# mdriver_v2.net
KiCad netlist of a schematic drawn in EAGLE
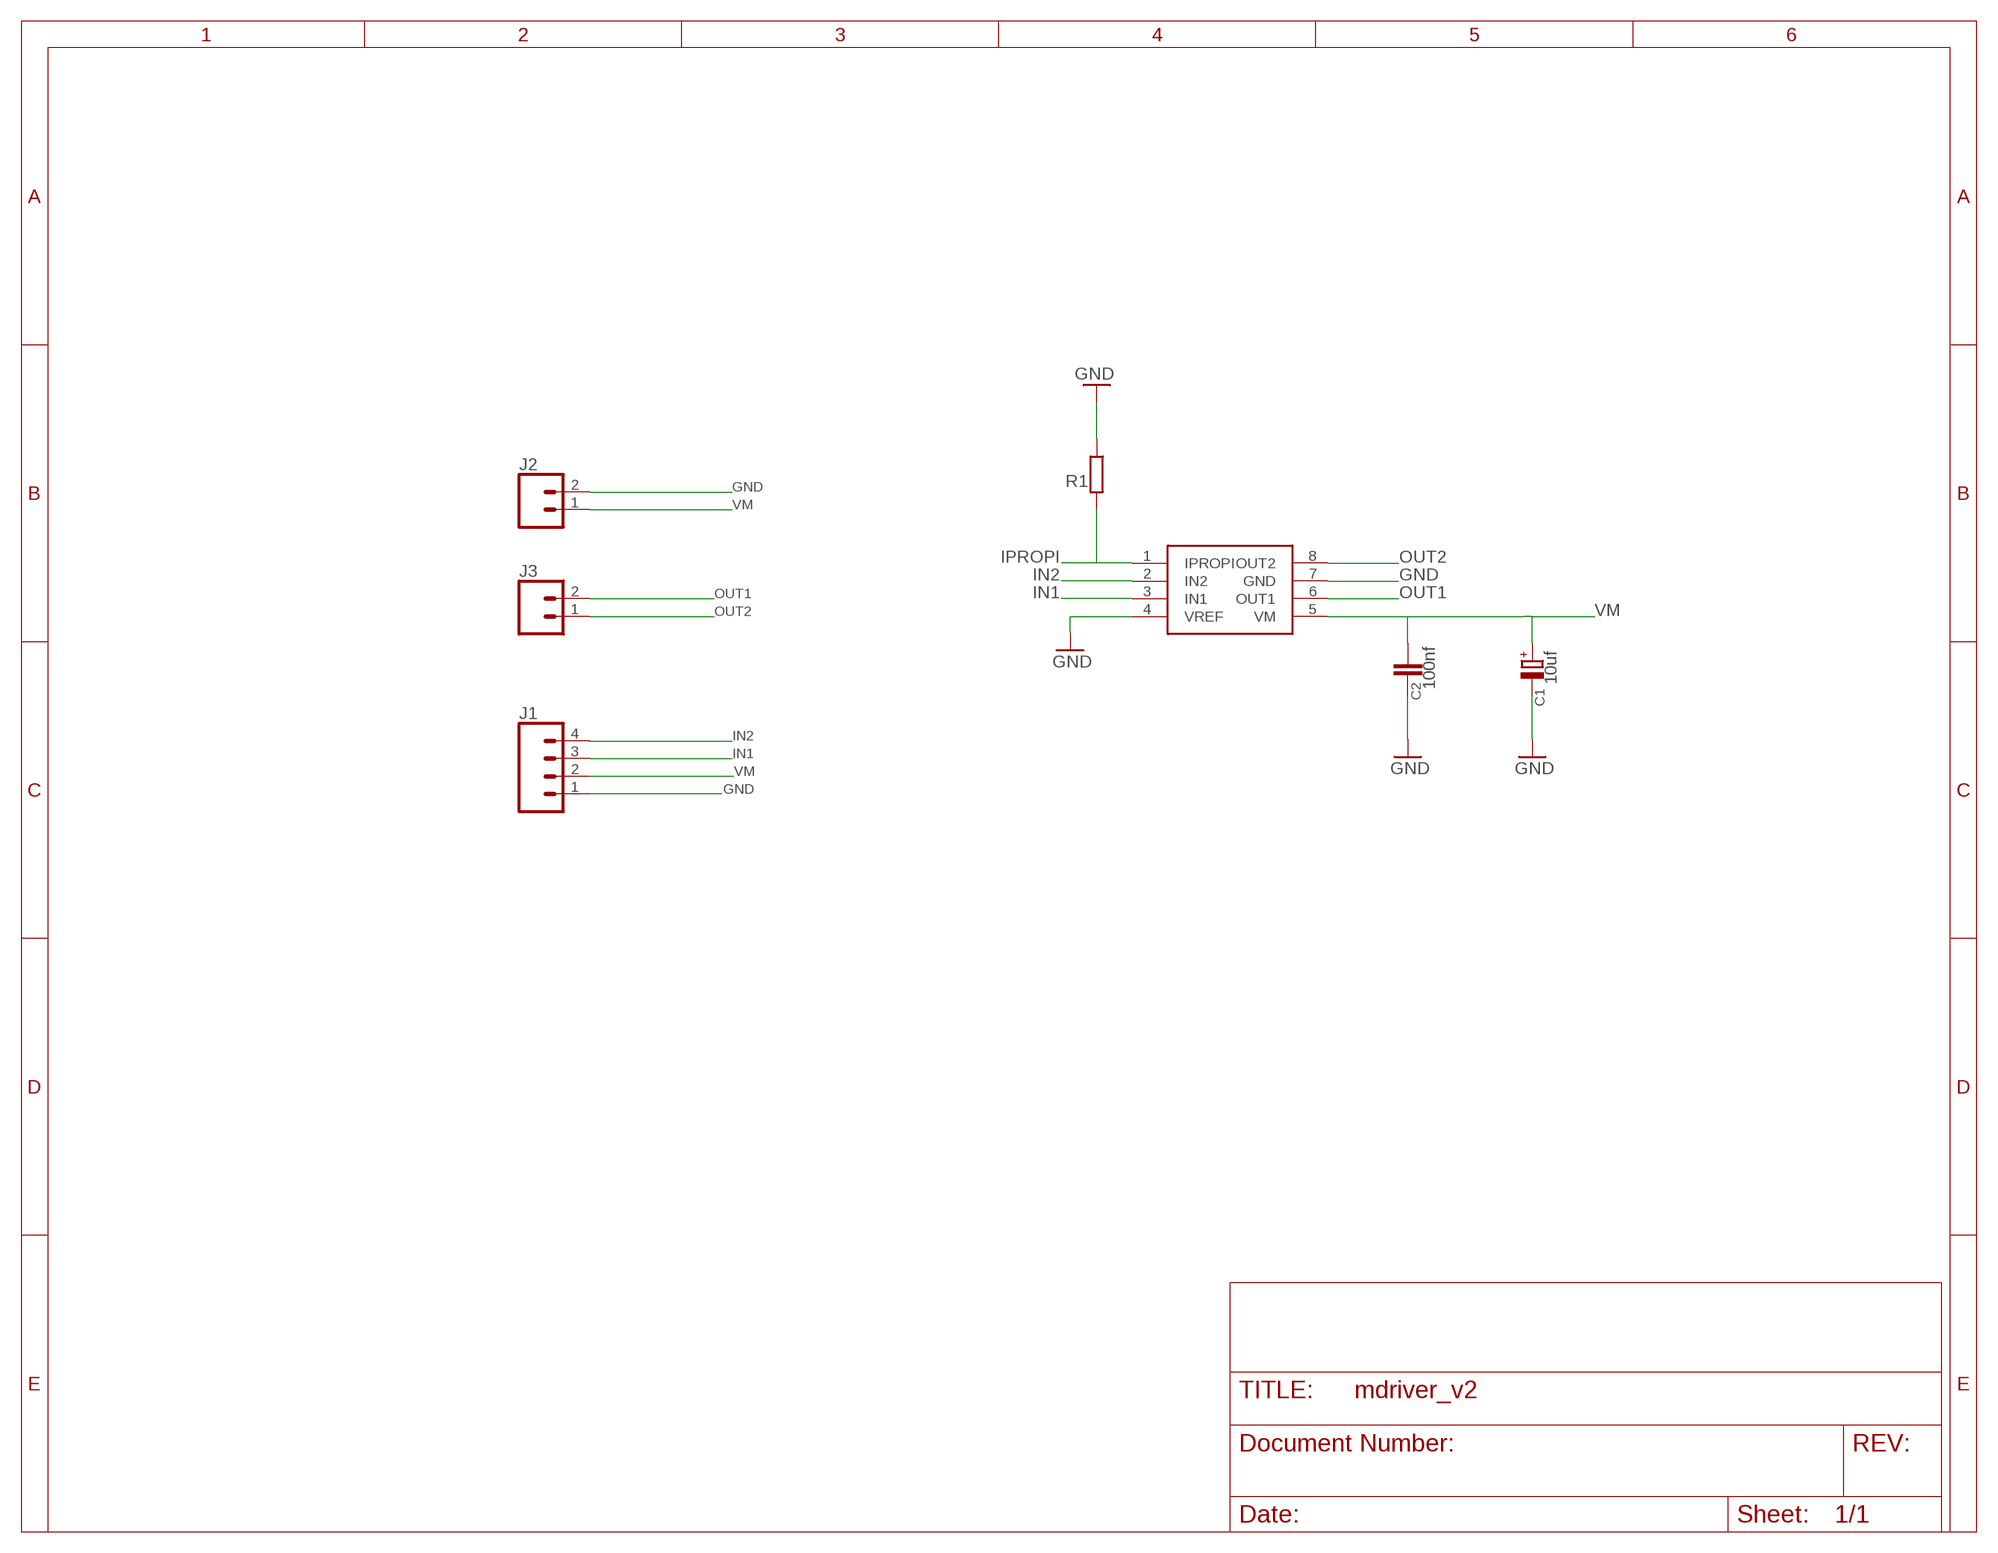
[diagram p0: schematic, sheet 1]

(export (version "E")
  (design (tool "Eeschema 10.0.6"))
  (components
    (comp (ref "C1")
      (value "10uf")
      (footprint "eagle-import:E2,5-6E")
      (libsource (lib "eagle-import") (part "CPOL-EUE2,5-6E"))
    )
    (comp (ref "C2")
      (value "100nf")
      (footprint "eagle-import:C025-025X050")
      (libsource (lib "eagle-import") (part "C-EU025-025X050"))
    )
    (comp (ref "J1")
      (value "CONN_04")
      (footprint "eagle-import:1X04")
      (libsource (lib "eagle-import") (part "CONN_04"))
    )
    (comp (ref "J2")
      (value "CONN_02")
      (footprint "eagle-import:1X02")
      (libsource (lib "eagle-import") (part "CONN_02"))
    )
    (comp (ref "J3")
      (value "CONN_02")
      (footprint "eagle-import:1X02")
      (libsource (lib "eagle-import") (part "CONN_02"))
    )
    (comp (ref "R1")
      (value "SMK")
      (footprint "eagle-import:SMK")
      (libsource (lib "eagle-import") (part "SMK"))
    )
    (comp (ref "U$1")
      (value "DRV8231A")
      (footprint "eagle-import:SOIC127P580X170-9T271X340N")
      (libsource (lib "eagle-import") (part "DRV8231A"))
    )
  )
  (nets
    (net (code "1") (name "/IN1") (class "Default")
      (node (ref "J1") (pin "3") (pinfunction "3_3") (pintype "passive"))
      (node (ref "U$1") (pin "3") (pinfunction "IN1_3") (pintype "bidirectional"))
    )
    (net (code "2") (name "/IN2") (class "Default")
      (node (ref "J1") (pin "4") (pinfunction "4_4") (pintype "passive"))
      (node (ref "U$1") (pin "2") (pinfunction "IN2_2") (pintype "bidirectional"))
    )
    (net (code "3") (name "/IPROPI") (class "Default")
      (node (ref "R1") (pin "2") (pinfunction "2_2") (pintype "passive"))
      (node (ref "U$1") (pin "1") (pinfunction "IPROPI_1") (pintype "bidirectional"))
    )
    (net (code "4") (name "/OUT1") (class "Default")
      (node (ref "J3") (pin "2") (pinfunction "2_2") (pintype "passive"))
      (node (ref "U$1") (pin "6") (pinfunction "OUT1_6") (pintype "bidirectional"))
    )
    (net (code "5") (name "/OUT2") (class "Default")
      (node (ref "J3") (pin "1") (pinfunction "1_1") (pintype "passive"))
      (node (ref "U$1") (pin "8") (pinfunction "OUT2_8") (pintype "bidirectional"))
    )
    (net (code "6") (name "/VM") (class "Default")
      (node (ref "C1") (pin "+") (pinfunction "+_+") (pintype "passive"))
      (node (ref "C2") (pin "1") (pinfunction "1_1") (pintype "passive"))
      (node (ref "J1") (pin "2") (pinfunction "2_2") (pintype "passive"))
      (node (ref "J2") (pin "1") (pinfunction "1_1") (pintype "passive"))
      (node (ref "U$1") (pin "5") (pinfunction "VM_5") (pintype "bidirectional"))
    )
    (net (code "7") (name "GND") (class "Default")
      (node (ref "C1") (pin "-") (pinfunction "-_-") (pintype "passive"))
      (node (ref "C2") (pin "2") (pinfunction "2_2") (pintype "passive"))
      (node (ref "J1") (pin "1") (pinfunction "1_1") (pintype "passive"))
      (node (ref "J2") (pin "2") (pinfunction "2_2") (pintype "passive"))
      (node (ref "R1") (pin "1") (pinfunction "1_1") (pintype "passive"))
      (node (ref "U$1") (pin "4") (pinfunction "VREF_4") (pintype "bidirectional"))
      (node (ref "U$1") (pin "7") (pinfunction "GND_7") (pintype "bidirectional"))
    )
  )
)
